# February.net
KiCad netlist of a schematic drawn in EAGLE
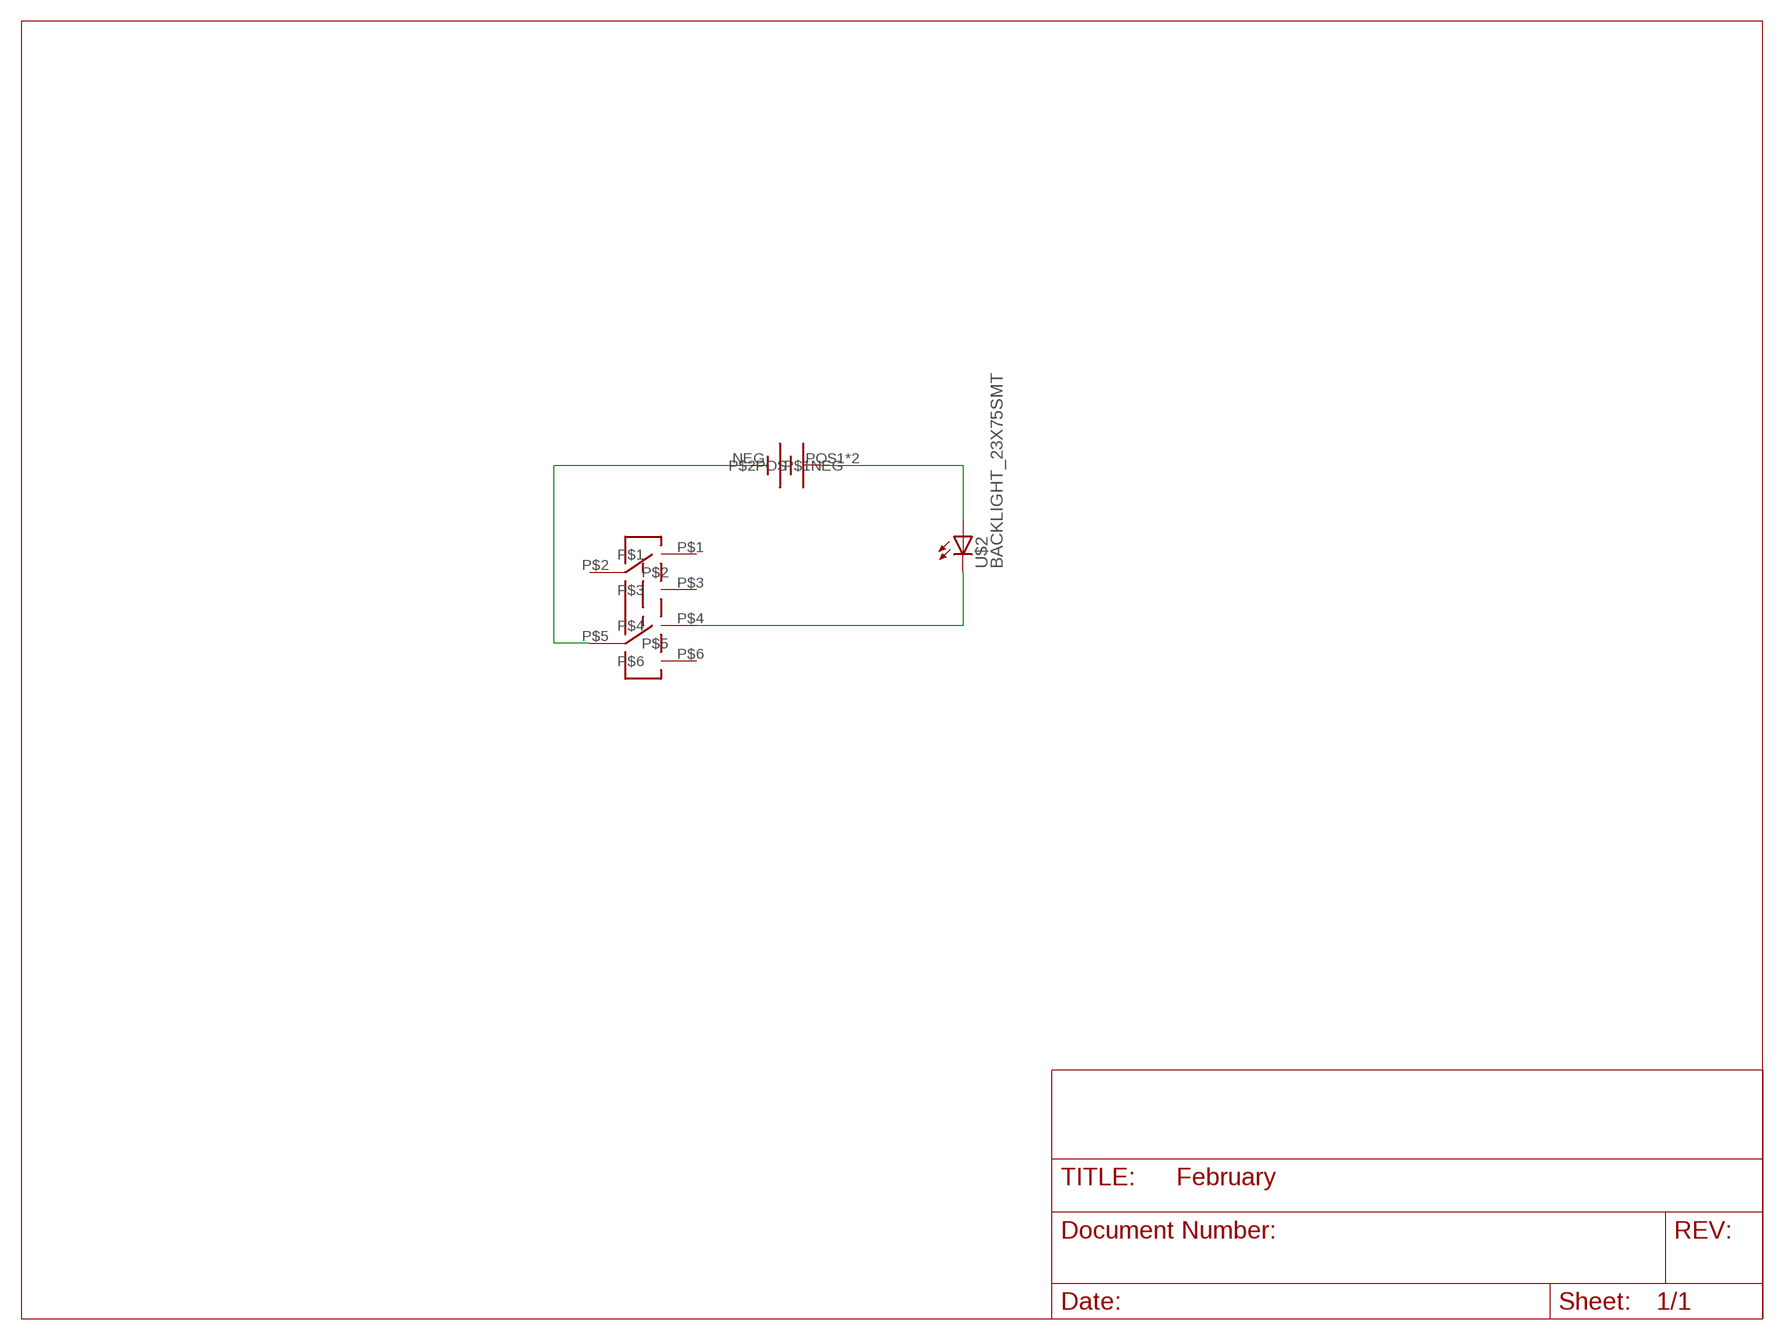
[diagram p0: schematic, sheet 1]

(export (version "E")
  (design (tool "Eeschema 10.0.6"))
  (components
    (comp (ref "U$1")
      (value "JS202011SCQN")
      (footprint "eagle-import:JS202011SCQN")
      (libsource (lib "eagle-import") (part "JS202011SCQN"))
    )
    (comp (ref "U$2")
      (value "BACKLIGHT_23X75SMT")
      (footprint "eagle-import:BACKLIGHT_23X75SMT")
      (libsource (lib "eagle-import") (part "BACKLIGHT_23X75SMT"))
    )
    (comp (ref "U$3")
      (value "BK-912")
      (footprint "eagle-import:BK-912")
      (libsource (lib "eagle-import") (part "BK-912"))
    )
  )
  (nets
    (net (code "1") (name "Net-(U$2-A)") (class "Default")
      (node (ref "U$2") (pin "LED+") (pinfunction "A_LED+") (pintype "passive"))
      (node (ref "U$3") (pin "POS1") (pinfunction "P$2POS_POS1") (pintype "bidirectional"))
      (node (ref "U$3") (pin "POS2") (pinfunction "P$2POS_POS2") (pintype "bidirectional"))
    )
    (net (code "2") (name "Net-(U$2-C)") (class "Default")
      (node (ref "U$1") (pin "P$4") (pinfunction "P$4_P$4") (pintype "bidirectional"))
      (node (ref "U$2") (pin "LED-") (pinfunction "C_LED-") (pintype "passive"))
    )
    (net (code "3") (name "Net-(U$3-P$1NEG)") (class "Default")
      (node (ref "U$1") (pin "P$5") (pinfunction "P$5_P$5") (pintype "bidirectional"))
      (node (ref "U$3") (pin "NEG") (pinfunction "P$1NEG_NEG") (pintype "bidirectional"))
    )
    (net (code "4") (name "unconnected-(U$1-PadP$1)") (class "Default")
      (node (ref "U$1") (pin "P$1") (pinfunction "P$1_P$1") (pintype "bidirectional"))
    )
    (net (code "5") (name "unconnected-(U$1-PadP$2)") (class "Default")
      (node (ref "U$1") (pin "P$2") (pinfunction "P$2_P$2") (pintype "bidirectional"))
    )
    (net (code "6") (name "unconnected-(U$1-PadP$3)") (class "Default")
      (node (ref "U$1") (pin "P$3") (pinfunction "P$3_P$3") (pintype "bidirectional"))
    )
    (net (code "7") (name "unconnected-(U$1-PadP$6)") (class "Default")
      (node (ref "U$1") (pin "P$6") (pinfunction "P$6_P$6") (pintype "bidirectional"))
    )
  )
)
